# BuckConverter.net
KiCad netlist of a schematic drawn in Altium Designer
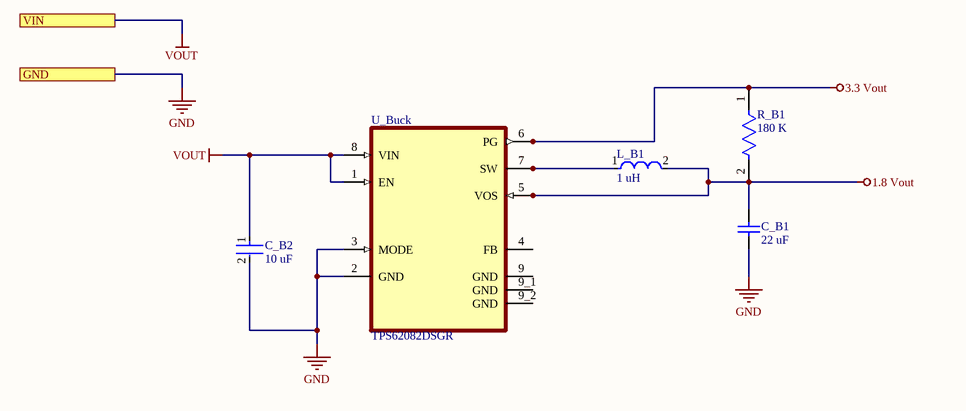
[diagram p0: BuckConverter.SchDoc]

(export (version "E")
  (design (tool "Eeschema 10.0.6"))
  (components
    (comp (ref "C_B1")
      (value "22 uF")
      (footprint "CAPC1608X100X20ML10")
      (description "Chip Capacitor, 22 uF, +/- 20%, 6.3 V, -55 to 85 degC, 1608 (0603 Metric), RoHS, Tape and Reel")
      (fields
        (field (name "TOLERANCE") "±20%")
        (field (name "PCN PART NUMBER") "MLCCPartNumberChange30/Nov/2012")
      )
      (libsource (lib "Altium Content Vault") (part "CAP-NP-2"))
    )
    (comp (ref "C_B2")
      (value "10 uF")
      (footprint "FP-C1608-MFG")
      (description "CAP CER 10UF 16V X5R 0603")
      (fields
        (field (name "OCTOPART") "https://octopart.com/c1608x5r1c106m080ab-tdk-26013480")
        (field (name "MANUFACTURER") "TDK Corporation")
      )
      (libsource (lib "Altium Content Vault") (part "11868f565c42a9108669ba33697ecf6"))
    )
    (comp (ref "L_B1")
      (value "1 uH")
      (footprint "FP-LQW15CN_10-MFG")
      (description "Wire Wound Ferrite type RF Inductor 1000nH ±20% 270mA 0.94Ω 0402 (1005)")
      (fields (field (name "TOLERANCE") "20%"))
      (libsource (lib "Altium Content Vault") (part "725321dda6339637d4d059423bc1c3c"))
    )
    (comp (ref "R_B1")
      (value "180 K")
      (footprint "FP-CPF0603-MFG")
      (description "RES SMD 180KΩ 0.1% 1/16W 0603")
      (fields
        (field (name "OCTOPART") "https://octopart.com/cpf0603b180ke-te+connectivity-23257790")
        (field (name "TOLERANCE") "0.1%")
      )
      (libsource (lib "Altium Content Vault") (part "1029c3af85768c4190bb7ad29bc67b5"))
    )
    (comp (ref "U_Buck")
      (value "TPS62082DSGR")
      (footprint "SON50P200X200X80-9N:SON50P200X200X80-9N")
      (description "1.2A High Efficient Step Down Converter in 2x2mm SON Package. 3.3 Vout (Min) 8-WSON -40 to 125")
      (fields (field (name "MF") "Texas Instruments") (field (name "DIGI-KEY_PART_NUMBER") "296-49331-1-ND"))
      (libsource (lib "TPS62082DSGR") (part "TPS62082DSGR"))
    )
  )
  (nets
    (net (code "1") (name "1.8 Vout") (class "Default")
      (node (ref "C_B1") (pin "2") (pinfunction "2_2") (pintype "passive"))
      (node (ref "L_B1") (pin "2") (pinfunction "2_2") (pintype "passive"))
      (node (ref "R_B1") (pin "2") (pinfunction "2_2") (pintype "passive"))
      (node (ref "U_Buck") (pin "5") (pinfunction "VOS_5") (pintype "input"))
    )
    (net (code "2") (name "3.3 Vout") (class "Default")
      (node (ref "R_B1") (pin "1") (pinfunction "1_1") (pintype "passive"))
      (node (ref "U_Buck") (pin "6") (pinfunction "PG_6") (pintype "output"))
    )
    (net (code "3") (name "GND") (class "Default")
      (node (ref "C_B1") (pin "1") (pinfunction "1_1") (pintype "passive"))
      (node (ref "C_B2") (pin "2") (pinfunction "2_2") (pintype "passive"))
      (node (ref "U_Buck") (pin "2") (pinfunction "GND_2") (pintype "power_in"))
      (node (ref "U_Buck") (pin "3") (pinfunction "MODE_3") (pintype "input"))
    )
    (net (code "4") (name "Net-(U_Buck-SW)") (class "Default")
      (node (ref "L_B1") (pin "1") (pinfunction "1_1") (pintype "passive"))
      (node (ref "U_Buck") (pin "7") (pinfunction "SW_7") (pintype "power_in"))
    )
    (net (code "5") (name "VOUT") (class "Default")
      (node (ref "C_B2") (pin "1") (pinfunction "1_1") (pintype "passive"))
      (node (ref "U_Buck") (pin "1") (pinfunction "EN_1") (pintype "input"))
      (node (ref "U_Buck") (pin "8") (pinfunction "VIN_8") (pintype "input"))
    )
    (net (code "6") (name "unconnected-(U_Buck-FB-Pad4)") (class "Default")
      (node (ref "U_Buck") (pin "4") (pinfunction "FB_4") (pintype "passive"))
    )
    (net (code "7") (name "unconnected-(U_Buck-GND-Pad9)") (class "Default")
      (node (ref "U_Buck") (pin "9") (pinfunction "GND_9") (pintype "power_in"))
    )
    (net (code "8") (name "unconnected-(U_Buck-GND-Pad9_1)") (class "Default")
      (node (ref "U_Buck") (pin "9_1") (pinfunction "GND_9_1") (pintype "power_in"))
    )
    (net (code "9") (name "unconnected-(U_Buck-GND-Pad9_2)") (class "Default")
      (node (ref "U_Buck") (pin "9_2") (pinfunction "GND_9_2") (pintype "power_in"))
    )
  )
)
